# Trinkey-DualSwitch-Concept3.net
KiCad netlist of a schematic drawn in EAGLE
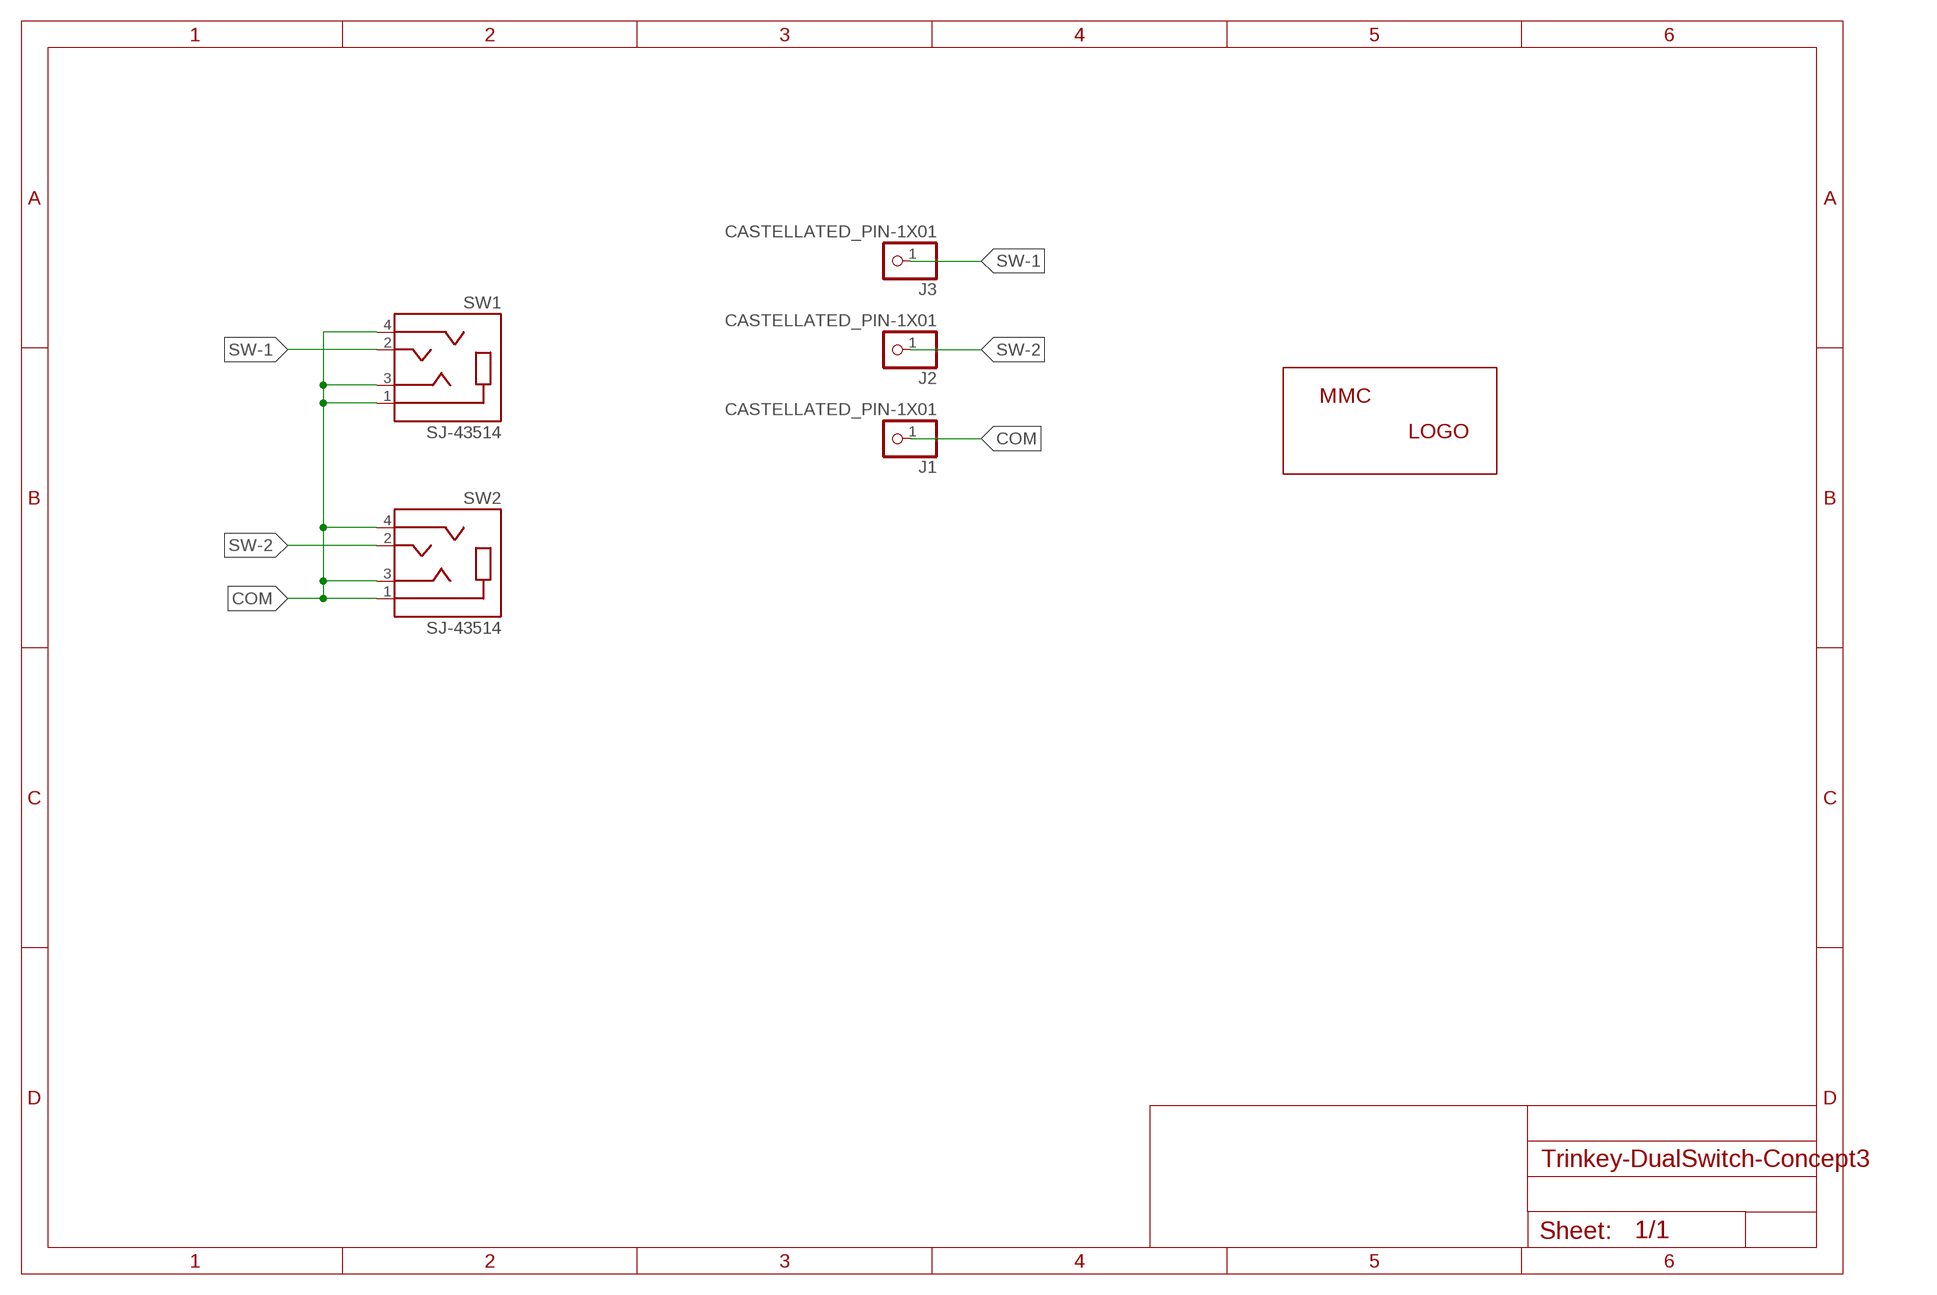
[diagram p0: schematic, sheet 1]

(export (version "E")
  (design (tool "Eeschema 10.0.6"))
  (components
    (comp (ref "J1")
      (value "CASTELLATED_PIN-1X01")
      (footprint "eagle-import:CASTELLATED_PIN-1X01")
      (libsource (lib "eagle-import") (part "CASTELLATED_PIN-1X01"))
    )
    (comp (ref "J2")
      (value "CASTELLATED_PIN-1X01")
      (footprint "eagle-import:CASTELLATED_PIN-1X01")
      (libsource (lib "eagle-import") (part "CASTELLATED_PIN-1X01"))
    )
    (comp (ref "J3")
      (value "CASTELLATED_PIN-1X01")
      (footprint "eagle-import:CASTELLATED_PIN-1X01")
      (libsource (lib "eagle-import") (part "CASTELLATED_PIN-1X01"))
    )
    (comp (ref "LABEL_LOGO")
      (value "MMC_LOGO-XSM")
      (footprint "eagle-import:MMC_X-SMALL_LOGO")
      (libsource (lib "eagle-import") (part "MMC_LOGO-XSM"))
    )
    (comp (ref "SW1")
      (value "SJ-43514")
      (footprint "eagle-import:CUI_SJ-43514")
      (libsource (lib "eagle-import") (part "SJ-43514"))
    )
    (comp (ref "SW2")
      (value "SJ-43514")
      (footprint "eagle-import:CUI_SJ-43514")
      (libsource (lib "eagle-import") (part "SJ-43514"))
    )
  )
  (nets
    (net (code "1") (name "COM") (class "Default")
      (node (ref "J1") (pin "1") (pinfunction "1_1") (pintype "passive"))
      (node (ref "SW1") (pin "1") (pinfunction "SLEEVE_1") (pintype "passive"))
      (node (ref "SW1") (pin "3") (pinfunction "RING1_3") (pintype "passive"))
      (node (ref "SW1") (pin "4") (pinfunction "RING2_4") (pintype "passive"))
      (node (ref "SW2") (pin "1") (pinfunction "SLEEVE_1") (pintype "passive"))
      (node (ref "SW2") (pin "3") (pinfunction "RING1_3") (pintype "passive"))
      (node (ref "SW2") (pin "4") (pinfunction "RING2_4") (pintype "passive"))
    )
    (net (code "2") (name "SW-1") (class "Default")
      (node (ref "J3") (pin "1") (pinfunction "1_1") (pintype "passive"))
      (node (ref "SW1") (pin "2") (pinfunction "TIP_2") (pintype "passive"))
    )
    (net (code "3") (name "SW-2") (class "Default")
      (node (ref "J2") (pin "1") (pinfunction "1_1") (pintype "passive"))
      (node (ref "SW2") (pin "2") (pinfunction "TIP_2") (pintype "passive"))
    )
  )
)
